# Power.net
KiCad netlist of a schematic drawn in Altium Designer
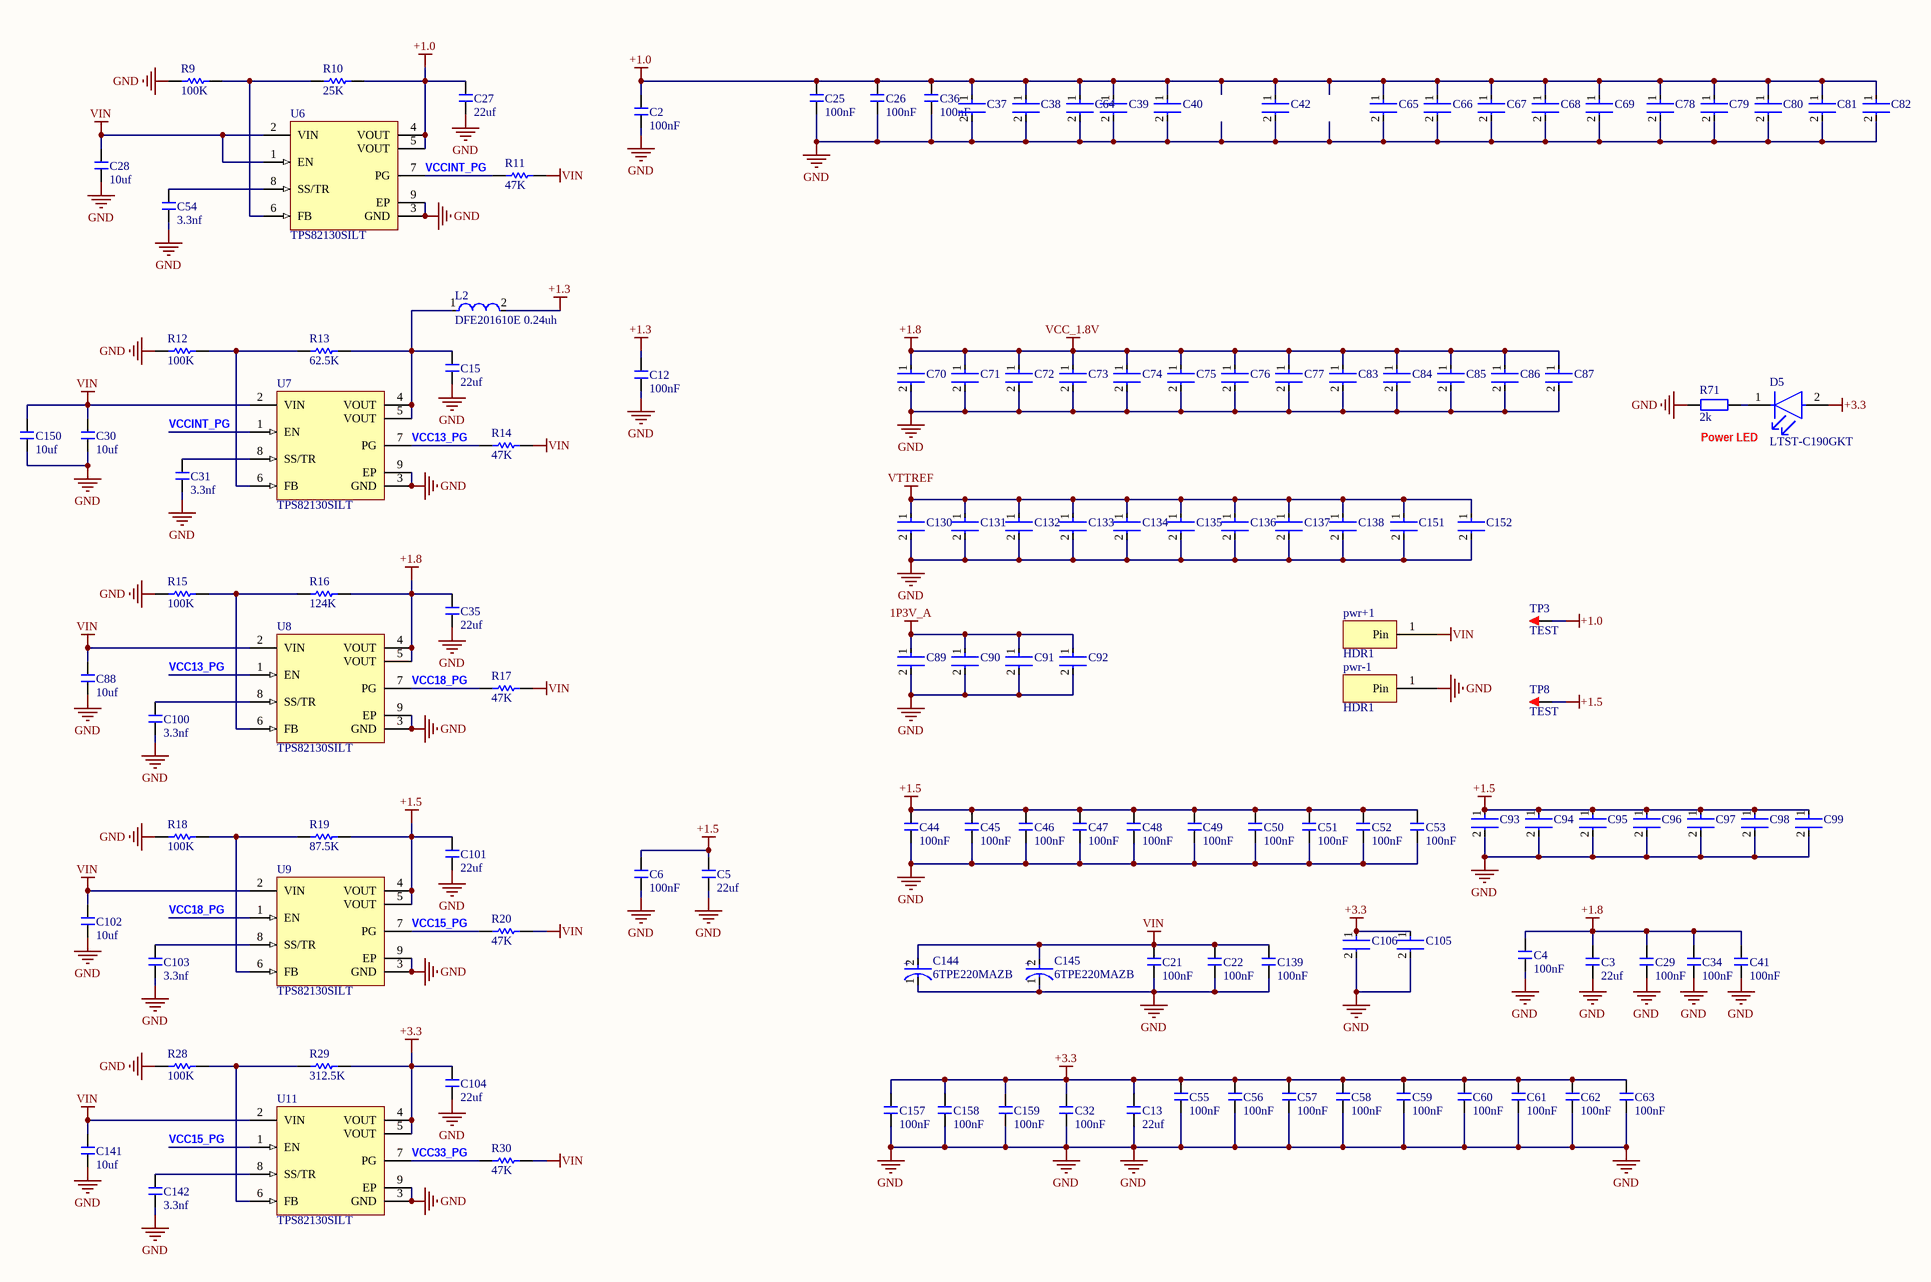
[diagram p0: Power.SchDoc]

(export (version "E")
  (design (tool "Eeschema 10.0.6"))
  (components
    (comp (ref "C2")
      (value "100nF")
      (footprint "SamacSys:CAP_0402")
      (description "无极性贴片电容")
      (libsource (lib "源创客") (part "C"))
    )
    (comp (ref "C3")
      (value "22uf")
      (footprint "SamacSys:CAP_0603")
      (description "无极性贴片电容")
      (libsource (lib "源创客") (part "C"))
    )
    (comp (ref "C4")
      (value "100nF")
      (footprint "SamacSys:CAP_0402")
      (description "无极性贴片电容")
      (libsource (lib "源创客") (part "C"))
    )
    (comp (ref "C5")
      (value "22uf")
      (footprint "SamacSys:CAP_0603")
      (description "无极性贴片电容")
      (libsource (lib "源创客") (part "C"))
    )
    (comp (ref "C6")
      (value "100nF")
      (footprint "SamacSys:CAP_0402")
      (description "无极性贴片电容")
      (libsource (lib "源创客") (part "C"))
    )
    (comp (ref "C12")
      (value "100nF")
      (footprint "SamacSys:CAP_0402")
      (description "无极性贴片电容")
      (libsource (lib "源创客") (part "C"))
    )
    (comp (ref "C13")
      (value "22uf")
      (footprint "SamacSys:CAP_0603")
      (description "无极性贴片电容")
      (libsource (lib "源创客") (part "C"))
    )
    (comp (ref "C15")
      (value "22uf")
      (footprint "SamacSys:CAP_0603")
      (description "无极性贴片电容")
      (libsource (lib "源创客") (part "C"))
    )
    (comp (ref "C21")
      (value "100nF")
      (footprint "SamacSys:CAP_0402")
      (description "无极性贴片电容")
      (libsource (lib "源创客") (part "C"))
    )
    (comp (ref "C22")
      (value "100nF")
      (footprint "SamacSys:CAP_0402")
      (description "无极性贴片电容")
      (libsource (lib "源创客") (part "C"))
    )
    (comp (ref "C25")
      (value "100nF")
      (footprint "SamacSys:CAP_0402")
      (description "无极性贴片电容")
      (libsource (lib "源创客") (part "C"))
    )
    (comp (ref "C26")
      (value "100nF")
      (footprint "SamacSys:CAP_0402")
      (description "无极性贴片电容")
      (libsource (lib "源创客") (part "C"))
    )
    (comp (ref "C27")
      (value "22uf")
      (footprint "SamacSys:CAP_0603")
      (description "无极性贴片电容")
      (libsource (lib "源创客") (part "C"))
    )
    (comp (ref "C28")
      (value "10uf")
      (footprint "SamacSys:CAP_0603")
      (description "无极性贴片电容")
      (libsource (lib "源创客") (part "C"))
    )
    (comp (ref "C29")
      (value "100nF")
      (footprint "SamacSys:CAP_0201")
      (description "无极性贴片电容")
      (libsource (lib "源创客") (part "C"))
    )
    (comp (ref "C30")
      (value "10uf")
      (footprint "SamacSys:CAP_0603")
      (description "无极性贴片电容")
      (libsource (lib "源创客") (part "C"))
    )
    (comp (ref "C31")
      (value "3.3nf")
      (footprint "SamacSys:CAP_0402")
      (description "无极性贴片电容")
      (libsource (lib "源创客") (part "C"))
    )
    (comp (ref "C32")
      (value "100nF")
      (footprint "SamacSys:CAP_0201")
      (description "无极性贴片电容")
      (libsource (lib "源创客") (part "C"))
    )
    (comp (ref "C34")
      (value "100nF")
      (footprint "SamacSys:CAP_0201")
      (description "无极性贴片电容")
      (libsource (lib "源创客") (part "C"))
    )
    (comp (ref "C35")
      (value "22uf")
      (footprint "SamacSys:CAP_0603")
      (description "无极性贴片电容")
      (libsource (lib "源创客") (part "C"))
    )
    (comp (ref "C36")
      (value "100nF")
      (footprint "SamacSys:CAP_0402")
      (description "无极性贴片电容")
      (libsource (lib "源创客") (part "C"))
    )
    (comp (ref "C37")
      (value "GRM033R61A104KE15D")
      (footprint "FP-GRM033-0_03-IPC_C")
      (description "Chip Multilayer Ceramic Capacitors for General Purpose, 0201, 0.10uF, X5R, 15%, 10%, 10V")
      (fields (field (name "TOLERANCE") "10%") (field (name "VOLTAGE") "10V"))
      (libsource (lib "Altium Content Vault") (part "b4654b650e69147ec39a6b967a45e02"))
    )
    (comp (ref "C38")
      (value "GRM033R61A104KE15D")
      (footprint "FP-GRM033-0_03-IPC_C")
      (description "Chip Multilayer Ceramic Capacitors for General Purpose, 0201, 0.10uF, X5R, 15%, 10%, 10V")
      (fields (field (name "TOLERANCE") "10%") (field (name "VOLTAGE") "10V"))
      (libsource (lib "Altium Content Vault") (part "b4654b650e69147ec39a6b967a45e02"))
    )
    (comp (ref "C39")
      (value "GRM033R61A104KE15D")
      (footprint "FP-GRM033-0_03-IPC_C")
      (description "Chip Multilayer Ceramic Capacitors for General Purpose, 0201, 0.10uF, X5R, 15%, 10%, 10V")
      (fields (field (name "TOLERANCE") "10%") (field (name "VOLTAGE") "10V"))
      (libsource (lib "Altium Content Vault") (part "b4654b650e69147ec39a6b967a45e02"))
    )
    (comp (ref "C40")
      (value "GRM033R61A104KE15D")
      (footprint "FP-GRM033-0_03-IPC_C")
      (description "Chip Multilayer Ceramic Capacitors for General Purpose, 0201, 0.10uF, X5R, 15%, 10%, 10V")
      (fields (field (name "TOLERANCE") "10%") (field (name "VOLTAGE") "10V"))
      (libsource (lib "Altium Content Vault") (part "b4654b650e69147ec39a6b967a45e02"))
    )
    (comp (ref "C41")
      (value "100nF")
      (footprint "SamacSys:CAP_0201")
      (description "无极性贴片电容")
      (libsource (lib "源创客") (part "C"))
    )
    (comp (ref "C42")
      (value "GRM033R61A104KE15D")
      (footprint "FP-GRM033-0_03-IPC_C")
      (description "Chip Multilayer Ceramic Capacitors for General Purpose, 0201, 0.10uF, X5R, 15%, 10%, 10V")
      (fields (field (name "TOLERANCE") "10%") (field (name "VOLTAGE") "10V"))
      (libsource (lib "Altium Content Vault") (part "b4654b650e69147ec39a6b967a45e02"))
    )
    (comp (ref "C44")
      (value "100nF")
      (footprint "SamacSys:CAP_0402")
      (description "无极性贴片电容")
      (libsource (lib "源创客") (part "C"))
    )
    (comp (ref "C45")
      (value "100nF")
      (footprint "SamacSys:CAP_0402")
      (description "无极性贴片电容")
      (libsource (lib "源创客") (part "C"))
    )
    (comp (ref "C46")
      (value "100nF")
      (footprint "SamacSys:CAP_0402")
      (description "无极性贴片电容")
      (libsource (lib "源创客") (part "C"))
    )
    (comp (ref "C47")
      (value "100nF")
      (footprint "SamacSys:CAP_0402")
      (description "无极性贴片电容")
      (libsource (lib "源创客") (part "C"))
    )
    (comp (ref "C48")
      (value "100nF")
      (footprint "SamacSys:CAP_0402")
      (description "无极性贴片电容")
      (libsource (lib "源创客") (part "C"))
    )
    (comp (ref "C49")
      (value "100nF")
      (footprint "SamacSys:CAP_0402")
      (description "无极性贴片电容")
      (libsource (lib "源创客") (part "C"))
    )
    (comp (ref "C50")
      (value "100nF")
      (footprint "SamacSys:CAP_0402")
      (description "无极性贴片电容")
      (libsource (lib "源创客") (part "C"))
    )
    (comp (ref "C51")
      (value "100nF")
      (footprint "SamacSys:CAP_0402")
      (description "无极性贴片电容")
      (libsource (lib "源创客") (part "C"))
    )
    (comp (ref "C52")
      (value "100nF")
      (footprint "SamacSys:CAP_0402")
      (description "无极性贴片电容")
      (libsource (lib "源创客") (part "C"))
    )
    (comp (ref "C53")
      (value "100nF")
      (footprint "SamacSys:CAP_0402")
      (description "无极性贴片电容")
      (libsource (lib "源创客") (part "C"))
    )
    (comp (ref "C54")
      (value "3.3nf")
      (footprint "SamacSys:CAP_0402")
      (description "无极性贴片电容")
      (libsource (lib "源创客") (part "C"))
    )
    (comp (ref "C55")
      (value "100nF")
      (footprint "SamacSys:CAP_0402")
      (description "无极性贴片电容")
      (libsource (lib "源创客") (part "C"))
    )
    (comp (ref "C56")
      (value "100nF")
      (footprint "SamacSys:CAP_0402")
      (description "无极性贴片电容")
      (libsource (lib "源创客") (part "C"))
    )
    (comp (ref "C57")
      (value "100nF")
      (footprint "SamacSys:CAP_0402")
      (description "无极性贴片电容")
      (libsource (lib "源创客") (part "C"))
    )
    (comp (ref "C58")
      (value "100nF")
      (footprint "SamacSys:CAP_0402")
      (description "无极性贴片电容")
      (libsource (lib "源创客") (part "C"))
    )
    (comp (ref "C59")
      (value "100nF")
      (footprint "SamacSys:CAP_0201")
      (description "无极性贴片电容")
      (libsource (lib "源创客") (part "C"))
    )
    (comp (ref "C60")
      (value "100nF")
      (footprint "SamacSys:CAP_0201")
      (description "无极性贴片电容")
      (libsource (lib "源创客") (part "C"))
    )
    (comp (ref "C61")
      (value "100nF")
      (footprint "SamacSys:CAP_0201")
      (description "无极性贴片电容")
      (libsource (lib "源创客") (part "C"))
    )
    (comp (ref "C62")
      (value "100nF")
      (footprint "SamacSys:CAP_0402")
      (description "无极性贴片电容")
      (libsource (lib "源创客") (part "C"))
    )
    (comp (ref "C63")
      (value "100nF")
      (footprint "SamacSys:CAP_0402")
      (description "无极性贴片电容")
      (libsource (lib "源创客") (part "C"))
    )
    (comp (ref "C64")
      (value "GRM033R61A104KE15D")
      (footprint "FP-GRM033-0_03-IPC_C")
      (description "Chip Multilayer Ceramic Capacitors for General Purpose, 0201, 0.10uF, X5R, 15%, 10%, 10V")
      (fields (field (name "TOLERANCE") "10%") (field (name "VOLTAGE") "10V"))
      (libsource (lib "Altium Content Vault") (part "b4654b650e69147ec39a6b967a45e02"))
    )
    (comp (ref "C65")
      (value "GRM033R61A104KE15D")
      (footprint "FP-GRM033-0_03-IPC_C")
      (description "Chip Multilayer Ceramic Capacitors for General Purpose, 0201, 0.10uF, X5R, 15%, 10%, 10V")
      (fields (field (name "TOLERANCE") "10%") (field (name "VOLTAGE") "10V"))
      (libsource (lib "Altium Content Vault") (part "b4654b650e69147ec39a6b967a45e02"))
    )
    (comp (ref "C66")
      (value "GRM033R61A104KE15D")
      (footprint "FP-GRM033-0_03-IPC_C")
      (description "Chip Multilayer Ceramic Capacitors for General Purpose, 0201, 0.10uF, X5R, 15%, 10%, 10V")
      (fields (field (name "TOLERANCE") "10%") (field (name "VOLTAGE") "10V"))
      (libsource (lib "Altium Content Vault") (part "b4654b650e69147ec39a6b967a45e02"))
    )
    (comp (ref "C67")
      (value "GRM033R61A104KE15D")
      (footprint "FP-GRM033-0_03-IPC_C")
      (description "Chip Multilayer Ceramic Capacitors for General Purpose, 0201, 0.10uF, X5R, 15%, 10%, 10V")
      (fields (field (name "TOLERANCE") "10%") (field (name "VOLTAGE") "10V"))
      (libsource (lib "Altium Content Vault") (part "b4654b650e69147ec39a6b967a45e02"))
    )
    (comp (ref "C68")
      (value "GRM033R61A104KE15D")
      (footprint "FP-GRM033-0_03-IPC_C")
      (description "Chip Multilayer Ceramic Capacitors for General Purpose, 0201, 0.10uF, X5R, 15%, 10%, 10V")
      (fields (field (name "TOLERANCE") "10%") (field (name "VOLTAGE") "10V"))
      (libsource (lib "Altium Content Vault") (part "b4654b650e69147ec39a6b967a45e02"))
    )
    (comp (ref "C69")
      (value "GRM033R61A104KE15D")
      (footprint "FP-GRM033-0_03-IPC_C")
      (description "Chip Multilayer Ceramic Capacitors for General Purpose, 0201, 0.10uF, X5R, 15%, 10%, 10V")
      (fields (field (name "TOLERANCE") "10%") (field (name "VOLTAGE") "10V"))
      (libsource (lib "Altium Content Vault") (part "b4654b650e69147ec39a6b967a45e02"))
    )
    (comp (ref "C70")
      (value "GRM033R61A104KE15D")
      (footprint "FP-GRM033-0_03-IPC_C")
      (description "Chip Multilayer Ceramic Capacitors for General Purpose, 0201, 0.10uF, X5R, 15%, 10%, 10V")
      (fields (field (name "TOLERANCE") "10%") (field (name "VOLTAGE") "10V"))
      (libsource (lib "Altium Content Vault") (part "b4654b650e69147ec39a6b967a45e02"))
    )
    (comp (ref "C71")
      (value "GRM033R61A104KE15D")
      (footprint "FP-GRM033-0_03-IPC_C")
      (description "Chip Multilayer Ceramic Capacitors for General Purpose, 0201, 0.10uF, X5R, 15%, 10%, 10V")
      (fields (field (name "TOLERANCE") "10%") (field (name "VOLTAGE") "10V"))
      (libsource (lib "Altium Content Vault") (part "b4654b650e69147ec39a6b967a45e02"))
    )
    (comp (ref "C72")
      (value "GRM033R61A104KE15D")
      (footprint "FP-GRM033-0_03-IPC_C")
      (description "Chip Multilayer Ceramic Capacitors for General Purpose, 0201, 0.10uF, X5R, 15%, 10%, 10V")
      (fields (field (name "TOLERANCE") "10%") (field (name "VOLTAGE") "10V"))
      (libsource (lib "Altium Content Vault") (part "b4654b650e69147ec39a6b967a45e02"))
    )
    (comp (ref "C73")
      (value "GRM033R61A104KE15D")
      (footprint "FP-GRM033-0_03-IPC_C")
      (description "Chip Multilayer Ceramic Capacitors for General Purpose, 0201, 0.10uF, X5R, 15%, 10%, 10V")
      (fields (field (name "TOLERANCE") "10%") (field (name "VOLTAGE") "10V"))
      (libsource (lib "Altium Content Vault") (part "b4654b650e69147ec39a6b967a45e02"))
    )
    (comp (ref "C74")
      (value "GRM033R61A104KE15D")
      (footprint "FP-GRM033-0_03-IPC_C")
      (description "Chip Multilayer Ceramic Capacitors for General Purpose, 0201, 0.10uF, X5R, 15%, 10%, 10V")
      (fields (field (name "TOLERANCE") "10%") (field (name "VOLTAGE") "10V"))
      (libsource (lib "Altium Content Vault") (part "b4654b650e69147ec39a6b967a45e02"))
    )
    (comp (ref "C75")
      (value "GRM033R61A104KE15D")
      (footprint "FP-GRM033-0_03-IPC_C")
      (description "Chip Multilayer Ceramic Capacitors for General Purpose, 0201, 0.10uF, X5R, 15%, 10%, 10V")
      (fields (field (name "TOLERANCE") "10%") (field (name "VOLTAGE") "10V"))
      (libsource (lib "Altium Content Vault") (part "b4654b650e69147ec39a6b967a45e02"))
    )
    (comp (ref "C76")
      (value "GRM033R61A104KE15D")
      (footprint "FP-GRM033-0_03-IPC_C")
      (description "Chip Multilayer Ceramic Capacitors for General Purpose, 0201, 0.10uF, X5R, 15%, 10%, 10V")
      (fields (field (name "TOLERANCE") "10%") (field (name "VOLTAGE") "10V"))
      (libsource (lib "Altium Content Vault") (part "b4654b650e69147ec39a6b967a45e02"))
    )
    (comp (ref "C77")
      (value "GRM033R61A104KE15D")
      (footprint "FP-GRM033-0_03-IPC_C")
      (description "Chip Multilayer Ceramic Capacitors for General Purpose, 0201, 0.10uF, X5R, 15%, 10%, 10V")
      (fields (field (name "TOLERANCE") "10%") (field (name "VOLTAGE") "10V"))
      (libsource (lib "Altium Content Vault") (part "b4654b650e69147ec39a6b967a45e02"))
    )
    (comp (ref "C78")
      (value "GRM033R61A104KE15D")
      (footprint "FP-GRM033-0_03-IPC_C")
      (description "Chip Multilayer Ceramic Capacitors for General Purpose, 0201, 0.10uF, X5R, 15%, 10%, 10V")
      (fields (field (name "TOLERANCE") "10%") (field (name "VOLTAGE") "10V"))
      (libsource (lib "Altium Content Vault") (part "b4654b650e69147ec39a6b967a45e02"))
    )
    (comp (ref "C79")
      (value "GRM033R61A104KE15D")
      (footprint "FP-GRM033-0_03-IPC_C")
      (description "Chip Multilayer Ceramic Capacitors for General Purpose, 0201, 0.10uF, X5R, 15%, 10%, 10V")
      (fields (field (name "TOLERANCE") "10%") (field (name "VOLTAGE") "10V"))
      (libsource (lib "Altium Content Vault") (part "b4654b650e69147ec39a6b967a45e02"))
    )
    (comp (ref "C80")
      (value "GRM033R61A104KE15D")
      (footprint "FP-GRM033-0_03-IPC_C")
      (description "Chip Multilayer Ceramic Capacitors for General Purpose, 0201, 0.10uF, X5R, 15%, 10%, 10V")
      (fields (field (name "TOLERANCE") "10%") (field (name "VOLTAGE") "10V"))
      (libsource (lib "Altium Content Vault") (part "b4654b650e69147ec39a6b967a45e02"))
    )
    (comp (ref "C81")
      (value "GRM033R61A104KE15D")
      (footprint "FP-GRM033-0_03-IPC_C")
      (description "Chip Multilayer Ceramic Capacitors for General Purpose, 0201, 0.10uF, X5R, 15%, 10%, 10V")
      (fields (field (name "TOLERANCE") "10%") (field (name "VOLTAGE") "10V"))
      (libsource (lib "Altium Content Vault") (part "b4654b650e69147ec39a6b967a45e02"))
    )
    (comp (ref "C82")
      (value "GRM033R61A104KE15D")
      (footprint "FP-GRM033-0_03-IPC_C")
      (description "Chip Multilayer Ceramic Capacitors for General Purpose, 0201, 0.10uF, X5R, 15%, 10%, 10V")
      (fields (field (name "TOLERANCE") "10%") (field (name "VOLTAGE") "10V"))
      (libsource (lib "Altium Content Vault") (part "b4654b650e69147ec39a6b967a45e02"))
    )
    (comp (ref "C83")
      (value "GRM033R61A104KE15D")
      (footprint "FP-GRM033-0_03-IPC_C")
      (description "Chip Multilayer Ceramic Capacitors for General Purpose, 0201, 0.10uF, X5R, 15%, 10%, 10V")
      (fields (field (name "TOLERANCE") "10%") (field (name "VOLTAGE") "10V"))
      (libsource (lib "Altium Content Vault") (part "b4654b650e69147ec39a6b967a45e02"))
    )
    (comp (ref "C84")
      (value "GRM033R61A104KE15D")
      (footprint "FP-GRM033-0_03-IPC_C")
      (description "Chip Multilayer Ceramic Capacitors for General Purpose, 0201, 0.10uF, X5R, 15%, 10%, 10V")
      (fields (field (name "TOLERANCE") "10%") (field (name "VOLTAGE") "10V"))
      (libsource (lib "Altium Content Vault") (part "b4654b650e69147ec39a6b967a45e02"))
    )
    (comp (ref "C85")
      (value "GRM033R61A104KE15D")
      (footprint "FP-GRM033-0_03-IPC_C")
      (description "Chip Multilayer Ceramic Capacitors for General Purpose, 0201, 0.10uF, X5R, 15%, 10%, 10V")
      (fields (field (name "TOLERANCE") "10%") (field (name "VOLTAGE") "10V"))
      (libsource (lib "Altium Content Vault") (part "b4654b650e69147ec39a6b967a45e02"))
    )
    (comp (ref "C86")
      (value "GRM033R61A104KE15D")
      (footprint "FP-GRM033-0_03-IPC_C")
      (description "Chip Multilayer Ceramic Capacitors for General Purpose, 0201, 0.10uF, X5R, 15%, 10%, 10V")
      (fields (field (name "TOLERANCE") "10%") (field (name "VOLTAGE") "10V"))
      (libsource (lib "Altium Content Vault") (part "b4654b650e69147ec39a6b967a45e02"))
    )
    (comp (ref "C87")
      (value "GRM033R61A104KE15D")
      (footprint "FP-GRM033-0_03-IPC_C")
      (description "Chip Multilayer Ceramic Capacitors for General Purpose, 0201, 0.10uF, X5R, 15%, 10%, 10V")
      (fields (field (name "TOLERANCE") "10%") (field (name "VOLTAGE") "10V"))
      (libsource (lib "Altium Content Vault") (part "b4654b650e69147ec39a6b967a45e02"))
    )
    (comp (ref "C88")
      (value "10uf")
      (footprint "SamacSys:CAP_0603")
      (description "无极性贴片电容")
      (libsource (lib "源创客") (part "C"))
    )
    (comp (ref "C89")
      (value "GRM033R61A104KE15D")
      (footprint "FP-GRM033-0_03-IPC_C")
      (description "Chip Multilayer Ceramic Capacitors for General Purpose, 0201, 0.10uF, X5R, 15%, 10%, 10V")
      (fields (field (name "TOLERANCE") "10%") (field (name "VOLTAGE") "10V"))
      (libsource (lib "Altium Content Vault") (part "b4654b650e69147ec39a6b967a45e02"))
    )
    (comp (ref "C90")
      (value "GRM033R61A104KE15D")
      (footprint "FP-GRM033-0_03-IPC_C")
      (description "Chip Multilayer Ceramic Capacitors for General Purpose, 0201, 0.10uF, X5R, 15%, 10%, 10V")
      (fields (field (name "TOLERANCE") "10%") (field (name "VOLTAGE") "10V"))
      (libsource (lib "Altium Content Vault") (part "b4654b650e69147ec39a6b967a45e02"))
    )
    (comp (ref "C91")
      (value "GRM033R61A104KE15D")
      (footprint "FP-GRM033-0_03-IPC_C")
      (description "Chip Multilayer Ceramic Capacitors for General Purpose, 0201, 0.10uF, X5R, 15%, 10%, 10V")
      (fields (field (name "TOLERANCE") "10%") (field (name "VOLTAGE") "10V"))
      (libsource (lib "Altium Content Vault") (part "b4654b650e69147ec39a6b967a45e02"))
    )
    (comp (ref "C92")
      (value "GRM033R61A104KE15D")
      (footprint "FP-GRM033-0_03-IPC_C")
      (description "Chip Multilayer Ceramic Capacitors for General Purpose, 0201, 0.10uF, X5R, 15%, 10%, 10V")
      (fields (field (name "TOLERANCE") "10%") (field (name "VOLTAGE") "10V"))
      (libsource (lib "Altium Content Vault") (part "b4654b650e69147ec39a6b967a45e02"))
    )
    (comp (ref "C93")
      (value "GRM033R61A104KE15D")
      (footprint "FP-GRM033-0_03-IPC_C")
      (description "Chip Multilayer Ceramic Capacitors for General Purpose, 0201, 0.10uF, X5R, 15%, 10%, 10V")
      (fields (field (name "TOLERANCE") "10%") (field (name "VOLTAGE") "10V"))
      (libsource (lib "Altium Content Vault") (part "b4654b650e69147ec39a6b967a45e02"))
    )
    (comp (ref "C94")
      (value "GRM033R61A104KE15D")
      (footprint "FP-GRM033-0_03-IPC_C")
      (description "Chip Multilayer Ceramic Capacitors for General Purpose, 0201, 0.10uF, X5R, 15%, 10%, 10V")
      (fields (field (name "TOLERANCE") "10%") (field (name "VOLTAGE") "10V"))
      (libsource (lib "Altium Content Vault") (part "b4654b650e69147ec39a6b967a45e02"))
    )
    (comp (ref "C95")
      (value "GRM033R61A104KE15D")
      (footprint "FP-GRM033-0_03-IPC_C")
      (description "Chip Multilayer Ceramic Capacitors for General Purpose, 0201, 0.10uF, X5R, 15%, 10%, 10V")
      (fields (field (name "TOLERANCE") "10%") (field (name "VOLTAGE") "10V"))
      (libsource (lib "Altium Content Vault") (part "b4654b650e69147ec39a6b967a45e02"))
    )
    (comp (ref "C96")
      (value "GRM033R61A104KE15D")
      (footprint "FP-GRM033-0_03-IPC_C")
      (description "Chip Multilayer Ceramic Capacitors for General Purpose, 0201, 0.10uF, X5R, 15%, 10%, 10V")
      (fields (field (name "TOLERANCE") "10%") (field (name "VOLTAGE") "10V"))
      (libsource (lib "Altium Content Vault") (part "b4654b650e69147ec39a6b967a45e02"))
    )
    (comp (ref "C97")
      (value "GRM033R61A104KE15D")
      (footprint "FP-GRM033-0_03-IPC_C")
      (description "Chip Multilayer Ceramic Capacitors for General Purpose, 0201, 0.10uF, X5R, 15%, 10%, 10V")
      (fields (field (name "TOLERANCE") "10%") (field (name "VOLTAGE") "10V"))
      (libsource (lib "Altium Content Vault") (part "b4654b650e69147ec39a6b967a45e02"))
    )
    (comp (ref "C98")
      (value "GRM033R61A104KE15D")
      (footprint "FP-GRM033-0_03-IPC_C")
      (description "Chip Multilayer Ceramic Capacitors for General Purpose, 0201, 0.10uF, X5R, 15%, 10%, 10V")
      (fields (field (name "TOLERANCE") "10%") (field (name "VOLTAGE") "10V"))
      (libsource (lib "Altium Content Vault") (part "b4654b650e69147ec39a6b967a45e02"))
    )
    (comp (ref "C99")
      (value "GRM033R61A104KE15D")
      (footprint "FP-GRM033-0_03-IPC_C")
      (description "Chip Multilayer Ceramic Capacitors for General Purpose, 0201, 0.10uF, X5R, 15%, 10%, 10V")
      (fields (field (name "TOLERANCE") "10%") (field (name "VOLTAGE") "10V"))
      (libsource (lib "Altium Content Vault") (part "b4654b650e69147ec39a6b967a45e02"))
    )
    (comp (ref "C100")
      (value "3.3nf")
      (footprint "SamacSys:CAP_0402")
      (description "无极性贴片电容")
      (libsource (lib "源创客") (part "C"))
    )
    (comp (ref "C101")
      (value "22uf")
      (footprint "SamacSys:CAP_0603")
      (description "无极性贴片电容")
      (libsource (lib "源创客") (part "C"))
    )
    (comp (ref "C102")
      (value "10uf")
      (footprint "SamacSys:CAP_0603")
      (description "无极性贴片电容")
      (libsource (lib "源创客") (part "C"))
    )
    (comp (ref "C103")
      (value "3.3nf")
      (footprint "SamacSys:CAP_0402")
      (description "无极性贴片电容")
      (libsource (lib "源创客") (part "C"))
    )
    (comp (ref "C104")
      (value "22uf")
      (footprint "SamacSys:CAP_0603")
      (description "无极性贴片电容")
      (libsource (lib "源创客") (part "C"))
    )
    (comp (ref "C105")
      (value "GRM033R61A104KE15D")
      (footprint "FP-GRM033-0_03-IPC_C")
      (description "Chip Multilayer Ceramic Capacitors for General Purpose, 0201, 0.10uF, X5R, 15%, 10%, 10V")
      (fields (field (name "TOLERANCE") "10%") (field (name "VOLTAGE") "10V"))
      (libsource (lib "Altium Content Vault") (part "b4654b650e69147ec39a6b967a45e02"))
    )
    (comp (ref "C106")
      (value "GRM033R61A104KE15D")
      (footprint "FP-GRM033-0_03-IPC_C")
      (description "Chip Multilayer Ceramic Capacitors for General Purpose, 0201, 0.10uF, X5R, 15%, 10%, 10V")
      (fields (field (name "TOLERANCE") "10%") (field (name "VOLTAGE") "10V"))
      (libsource (lib "Altium Content Vault") (part "b4654b650e69147ec39a6b967a45e02"))
    )
    (comp (ref "C130")
      (value "GRM033R61A104KE15D")
      (footprint "FP-GRM033-0_03-IPC_C")
      (description "Chip Multilayer Ceramic Capacitors for General Purpose, 0201, 0.10uF, X5R, 15%, 10%, 10V")
      (fields (field (name "TOLERANCE") "10%") (field (name "VOLTAGE") "10V"))
      (libsource (lib "Altium Content Vault") (part "b4654b650e69147ec39a6b967a45e02"))
    )
    (comp (ref "C131")
      (value "GRM033R61A104KE15D")
      (footprint "FP-GRM033-0_03-IPC_C")
      (description "Chip Multilayer Ceramic Capacitors for General Purpose, 0201, 0.10uF, X5R, 15%, 10%, 10V")
      (fields (field (name "TOLERANCE") "10%") (field (name "VOLTAGE") "10V"))
      (libsource (lib "Altium Content Vault") (part "b4654b650e69147ec39a6b967a45e02"))
    )
    (comp (ref "C132")
      (value "GRM033R61A104KE15D")
      (footprint "FP-GRM033-0_03-IPC_C")
      (description "Chip Multilayer Ceramic Capacitors for General Purpose, 0201, 0.10uF, X5R, 15%, 10%, 10V")
      (fields (field (name "TOLERANCE") "10%") (field (name "VOLTAGE") "10V"))
      (libsource (lib "Altium Content Vault") (part "b4654b650e69147ec39a6b967a45e02"))
    )
    (comp (ref "C133")
      (value "GRM033R61A104KE15D")
      (footprint "FP-GRM033-0_03-IPC_C")
      (description "Chip Multilayer Ceramic Capacitors for General Purpose, 0201, 0.10uF, X5R, 15%, 10%, 10V")
      (fields (field (name "TOLERANCE") "10%") (field (name "VOLTAGE") "10V"))
      (libsource (lib "Altium Content Vault") (part "b4654b650e69147ec39a6b967a45e02"))
    )
    (comp (ref "C134")
      (value "GRM033R61A104KE15D")
      (footprint "FP-GRM033-0_03-IPC_C")
      (description "Chip Multilayer Ceramic Capacitors for General Purpose, 0201, 0.10uF, X5R, 15%, 10%, 10V")
      (fields (field (name "TOLERANCE") "10%") (field (name "VOLTAGE") "10V"))
      (libsource (lib "Altium Content Vault") (part "b4654b650e69147ec39a6b967a45e02"))
    )
    (comp (ref "C135")
      (value "GRM033R61A104KE15D")
      (footprint "FP-GRM033-0_03-IPC_C")
      (description "Chip Multilayer Ceramic Capacitors for General Purpose, 0201, 0.10uF, X5R, 15%, 10%, 10V")
      (fields (field (name "TOLERANCE") "10%") (field (name "VOLTAGE") "10V"))
      (libsource (lib "Altium Content Vault") (part "b4654b650e69147ec39a6b967a45e02"))
    )
    (comp (ref "C136")
      (value "GRM033R61A104KE15D")
      (footprint "FP-GRM033-0_03-IPC_C")
      (description "Chip Multilayer Ceramic Capacitors for General Purpose, 0201, 0.10uF, X5R, 15%, 10%, 10V")
      (fields (field (name "TOLERANCE") "10%") (field (name "VOLTAGE") "10V"))
      (libsource (lib "Altium Content Vault") (part "b4654b650e69147ec39a6b967a45e02"))
    )
    (comp (ref "C137")
      (value "GRM033R61A104KE15D")
      (footprint "FP-GRM033-0_03-IPC_C")
      (description "Chip Multilayer Ceramic Capacitors for General Purpose, 0201, 0.10uF, X5R, 15%, 10%, 10V")
      (fields (field (name "TOLERANCE") "10%") (field (name "VOLTAGE") "10V"))
      (libsource (lib "Altium Content Vault") (part "b4654b650e69147ec39a6b967a45e02"))
    )
    (comp (ref "C138")
      (value "GRM033R61A104KE15D")
      (footprint "FP-GRM033-0_03-IPC_C")
      (description "Chip Multilayer Ceramic Capacitors for General Purpose, 0201, 0.10uF, X5R, 15%, 10%, 10V")
      (fields (field (name "TOLERANCE") "10%") (field (name "VOLTAGE") "10V"))
      (libsource (lib "Altium Content Vault") (part "b4654b650e69147ec39a6b967a45e02"))
    )
    (comp (ref "C139")
      (value "100nF")
      (footprint "SamacSys:CAP_0402")
      (description "无极性贴片电容")
      (libsource (lib "源创客") (part "C"))
    )
    (comp (ref "C141")
      (value "10uf")
      (footprint "SamacSys:CAP_0603")
      (description "无极性贴片电容")
      (libsource (lib "源创客") (part "C"))
    )
    (comp (ref "C142")
      (value "3.3nf")
      (footprint "SamacSys:CAP_0402")
      (description "无极性贴片电容")
      (libsource (lib "源创客") (part "C"))
    )
    (comp (ref "C144")
      (value "6TPE220MAZB")
      (footprint "FP-TPEB2-MFG")
      (description "CAP TANT POLY 220UF 6.3V 1411")
      (fields (field (name "TOLERANCE") "20%") (field (name "VOLTAGE") "6.3V"))
      (libsource (lib "Altium Content Vault") (part "a00bbbee19879c290e62620ae7e47b1"))
    )
    (comp (ref "C145")
      (value "6TPE220MAZB")
      (footprint "FP-TPEB2-MFG")
      (description "CAP TANT POLY 220UF 6.3V 1411")
      (fields (field (name "TOLERANCE") "20%") (field (name "VOLTAGE") "6.3V"))
      (libsource (lib "Altium Content Vault") (part "a00bbbee19879c290e62620ae7e47b1"))
    )
    (comp (ref "C150")
      (value "10uf")
      (footprint "SamacSys:CAP_0603")
      (description "无极性贴片电容")
      (libsource (lib "源创客") (part "C"))
    )
    (comp (ref "C151")
      (value "GRM033R61A104KE15D")
      (footprint "FP-GRM033-0_03-IPC_C")
      (description "Chip Multilayer Ceramic Capacitors for General Purpose, 0201, 0.10uF, X5R, 15%, 10%, 10V")
      (fields (field (name "TOLERANCE") "10%") (field (name "VOLTAGE") "10V"))
      (libsource (lib "Altium Content Vault") (part "b4654b650e69147ec39a6b967a45e02"))
    )
    (comp (ref "C152")
      (value "GRM033R61A104KE15D")
      (footprint "FP-GRM033-0_03-IPC_C")
      (description "Chip Multilayer Ceramic Capacitors for General Purpose, 0201, 0.10uF, X5R, 15%, 10%, 10V")
      (fields (field (name "TOLERANCE") "10%") (field (name "VOLTAGE") "10V"))
      (libsource (lib "Altium Content Vault") (part "b4654b650e69147ec39a6b967a45e02"))
    )
    (comp (ref "C157")
      (value "100nF")
      (footprint "SamacSys:CAP_0201")
      (description "无极性贴片电容")
      (libsource (lib "源创客") (part "C"))
    )
    (comp (ref "C158")
      (value "100nF")
      (footprint "SamacSys:CAP_0201")
      (description "无极性贴片电容")
      (libsource (lib "源创客") (part "C"))
    )
    (comp (ref "C159")
      (value "100nF")
      (footprint "SamacSys:CAP_0201")
      (description "无极性贴片电容")
      (libsource (lib "源创客") (part "C"))
    )
    (comp (ref "D5")
      (value "LTST-C190GKT")
      (footprint "FP-LTST-C190GKT-MFG")
      (description "LED GREEN CLEAR CHIP SMD")
      (fields (field (name "VOLTAGE") "2V"))
      (libsource (lib "Altium Content Vault") (part "8706943c75ba83719d021d2fdc84c58"))
    )
    (comp (ref "L2")
      (value "DFE201610E 0.24uh")
      (footprint "FP-DFE201610C-MFG")
      (description "0.24uh")
      (libsource (lib "Altium Content Vault") (part "725321dda6339637d4d059423bc1c3c"))
    )
    (comp (ref "pwr+1") (value "HDR1") (footprint "SamacSys:HDR1") (libsource (lib "SamacSys") (part "HDR1")))
    (comp (ref "pwr-1") (value "HDR1") (footprint "SamacSys:HDR1") (libsource (lib "SamacSys") (part "HDR1")))
    (comp (ref "R9") (value "100K") (footprint "SamacSys:RES_0402") (libsource (lib "电阻") (part "RES")))
    (comp (ref "R10") (value "25K") (footprint "SamacSys:RES_0402") (libsource (lib "电阻") (part "RES")))
    (comp (ref "R11") (value "47K") (footprint "SamacSys:RES_0402") (libsource (lib "电阻") (part "RES")))
    (comp (ref "R12") (value "100K") (footprint "SamacSys:RES_0402") (libsource (lib "电阻") (part "RES")))
    (comp (ref "R13") (value "62.5K") (footprint "SamacSys:RES_0402") (libsource (lib "电阻") (part "RES")))
    (comp (ref "R14") (value "47K") (footprint "SamacSys:RES_0402") (libsource (lib "电阻") (part "RES")))
    (comp (ref "R15") (value "100K") (footprint "SamacSys:RES_0402") (libsource (lib "电阻") (part "RES")))
    (comp (ref "R16") (value "124K") (footprint "SamacSys:RES_0402") (libsource (lib "电阻") (part "RES")))
    (comp (ref "R17") (value "47K") (footprint "SamacSys:RES_0402") (libsource (lib "电阻") (part "RES")))
    (comp (ref "R18") (value "100K") (footprint "SamacSys:RES_0402") (libsource (lib "电阻") (part "RES")))
    (comp (ref "R19") (value "87.5K") (footprint "SamacSys:RES_0402") (libsource (lib "电阻") (part "RES")))
    (comp (ref "R20") (value "47K") (footprint "SamacSys:RES_0402") (libsource (lib "电阻") (part "RES")))
    (comp (ref "R28") (value "100K") (footprint "SamacSys:RES_0402") (libsource (lib "电阻") (part "RES")))
    (comp (ref "R29") (value "312.5K") (footprint "SamacSys:RES_0402") (libsource (lib "电阻") (part "RES")))
    (comp (ref "R30") (value "47K") (footprint "SamacSys:RES_0402") (libsource (lib "电阻") (part "RES")))
    (comp (ref "R71")
      (value "2k")
      (footprint "SamacSys:RES_0402")
      (description "贴片电阻")
      (libsource (lib "源创客") (part "R"))
    )
    (comp (ref "TP3")
      (value "TEST")
      (footprint "TEST 0.8")
      (description "测试点")
      (libsource (lib "源创客") (part "TEST"))
    )
    (comp (ref "TP8")
      (value "TEST")
      (footprint "TEST 0.8")
      (description "测试点")
      (libsource (lib "源创客") (part "TEST"))
    )
    (comp (ref "U6")
      (value "TPS82130SILT")
      (footprint "SIL0008D_V")
      (fields (field (name "MANUFACTURER") "Texas Instruments"))
      (libsource (lib "Altium Content Vault") (part "TI-TPS82130-SIL-8"))
    )
    (comp (ref "U7")
      (value "TPS82130SILT")
      (footprint "SIL0008D_V")
      (fields (field (name "MANUFACTURER") "Texas Instruments"))
      (libsource (lib "Altium Content Vault") (part "TI-TPS82130-SIL-8"))
    )
    (comp (ref "U8")
      (value "TPS82130SILT")
      (footprint "SIL0008D_V")
      (fields (field (name "MANUFACTURER") "Texas Instruments"))
      (libsource (lib "Altium Content Vault") (part "TI-TPS82130-SIL-8"))
    )
    (comp (ref "U9")
      (value "TPS82130SILT")
      (footprint "SIL0008D_V")
      (fields (field (name "MANUFACTURER") "Texas Instruments"))
      (libsource (lib "Altium Content Vault") (part "TI-TPS82130-SIL-8"))
    )
    (comp (ref "U11")
      (value "TPS82130SILT")
      (footprint "SIL0008D_V")
      (fields (field (name "MANUFACTURER") "Texas Instruments"))
      (libsource (lib "Altium Content Vault") (part "TI-TPS82130-SIL-8"))
    )
  )
  (nets
    (net (code "1") (name "+1.0") (class "Default")
      (node (ref "C2") (pin "1") (pinfunction "1_1") (pintype "passive"))
      (node (ref "C25") (pin "1") (pinfunction "1_1") (pintype "passive"))
      (node (ref "C26") (pin "1") (pinfunction "1_1") (pintype "passive"))
      (node (ref "C27") (pin "2") (pinfunction "2_2") (pintype "passive"))
      (node (ref "C36") (pin "1") (pinfunction "1_1") (pintype "passive"))
      (node (ref "C37") (pin "1") (pinfunction "1_1") (pintype "passive"))
      (node (ref "C38") (pin "1") (pinfunction "1_1") (pintype "passive"))
      (node (ref "C39") (pin "1") (pinfunction "1_1") (pintype "passive"))
      (node (ref "C40") (pin "1") (pinfunction "1_1") (pintype "passive"))
      (node (ref "C42") (pin "1") (pinfunction "1_1") (pintype "passive"))
      (node (ref "C64") (pin "1") (pinfunction "1_1") (pintype "passive"))
      (node (ref "C65") (pin "1") (pinfunction "1_1") (pintype "passive"))
      (node (ref "C66") (pin "1") (pinfunction "1_1") (pintype "passive"))
      (node (ref "C67") (pin "1") (pinfunction "1_1") (pintype "passive"))
      (node (ref "C68") (pin "1") (pinfunction "1_1") (pintype "passive"))
      (node (ref "C69") (pin "1") (pinfunction "1_1") (pintype "passive"))
      (node (ref "C78") (pin "1") (pinfunction "1_1") (pintype "passive"))
      (node (ref "C79") (pin "1") (pinfunction "1_1") (pintype "passive"))
      (node (ref "C80") (pin "1") (pinfunction "1_1") (pintype "passive"))
      (node (ref "C81") (pin "1") (pinfunction "1_1") (pintype "passive"))
      (node (ref "C82") (pin "1") (pinfunction "1_1") (pintype "passive"))
      (node (ref "R10") (pin "1") (pinfunction "1_1") (pintype "passive"))
      (node (ref "TP3") (pin "1") (pinfunction "1_1") (pintype "passive"))
      (node (ref "U6") (pin "4") (pinfunction "VOUT_4") (pintype "power_in"))
      (node (ref "U6") (pin "5") (pinfunction "VOUT_5") (pintype "power_in"))
    )
    (net (code "2") (name "+1.3") (class "Default")
      (node (ref "C12") (pin "1") (pinfunction "1_1") (pintype "passive"))
      (node (ref "L2") (pin "2") (pinfunction "2_2") (pintype "passive"))
    )
    (net (code "3") (name "+1.5") (class "Default")
      (node (ref "C101") (pin "2") (pinfunction "2_2") (pintype "passive"))
      (node (ref "C44") (pin "1") (pinfunction "1_1") (pintype "passive"))
      (node (ref "C45") (pin "1") (pinfunction "1_1") (pintype "passive"))
      (node (ref "C46") (pin "1") (pinfunction "1_1") (pintype "passive"))
      (node (ref "C47") (pin "1") (pinfunction "1_1") (pintype "passive"))
      (node (ref "C48") (pin "1") (pinfunction "1_1") (pintype "passive"))
      (node (ref "C49") (pin "1") (pinfunction "1_1") (pintype "passive"))
      (node (ref "C5") (pin "2") (pinfunction "2_2") (pintype "passive"))
      (node (ref "C50") (pin "1") (pinfunction "1_1") (pintype "passive"))
      (node (ref "C51") (pin "1") (pinfunction "1_1") (pintype "passive"))
      (node (ref "C52") (pin "1") (pinfunction "1_1") (pintype "passive"))
      (node (ref "C53") (pin "1") (pinfunction "1_1") (pintype "passive"))
      (node (ref "C6") (pin "1") (pinfunction "1_1") (pintype "passive"))
      (node (ref "C93") (pin "1") (pinfunction "1_1") (pintype "passive"))
      (node (ref "C94") (pin "1") (pinfunction "1_1") (pintype "passive"))
      (node (ref "C95") (pin "1") (pinfunction "1_1") (pintype "passive"))
      (node (ref "C96") (pin "1") (pinfunction "1_1") (pintype "passive"))
      (node (ref "C97") (pin "1") (pinfunction "1_1") (pintype "passive"))
      (node (ref "C98") (pin "1") (pinfunction "1_1") (pintype "passive"))
      (node (ref "C99") (pin "1") (pinfunction "1_1") (pintype "passive"))
      (node (ref "R19") (pin "1") (pinfunction "1_1") (pintype "passive"))
      (node (ref "TP8") (pin "1") (pinfunction "1_1") (pintype "passive"))
      (node (ref "U9") (pin "4") (pinfunction "VOUT_4") (pintype "power_in"))
      (node (ref "U9") (pin "5") (pinfunction "VOUT_5") (pintype "power_in"))
    )
    (net (code "4") (name "+1.8") (class "Default")
      (node (ref "C29") (pin "1") (pinfunction "1_1") (pintype "passive"))
      (node (ref "C3") (pin "2") (pinfunction "2_2") (pintype "passive"))
      (node (ref "C34") (pin "1") (pinfunction "1_1") (pintype "passive"))
      (node (ref "C35") (pin "2") (pinfunction "2_2") (pintype "passive"))
      (node (ref "C4") (pin "1") (pinfunction "1_1") (pintype "passive"))
      (node (ref "C41") (pin "1") (pinfunction "1_1") (pintype "passive"))
      (node (ref "C70") (pin "1") (pinfunction "1_1") (pintype "passive"))
      (node (ref "C71") (pin "1") (pinfunction "1_1") (pintype "passive"))
      (node (ref "C72") (pin "1") (pinfunction "1_1") (pintype "passive"))
      (node (ref "C73") (pin "1") (pinfunction "1_1") (pintype "passive"))
      (node (ref "C74") (pin "1") (pinfunction "1_1") (pintype "passive"))
      (node (ref "C75") (pin "1") (pinfunction "1_1") (pintype "passive"))
      (node (ref "C76") (pin "1") (pinfunction "1_1") (pintype "passive"))
      (node (ref "C77") (pin "1") (pinfunction "1_1") (pintype "passive"))
      (node (ref "C83") (pin "1") (pinfunction "1_1") (pintype "passive"))
      (node (ref "C84") (pin "1") (pinfunction "1_1") (pintype "passive"))
      (node (ref "C85") (pin "1") (pinfunction "1_1") (pintype "passive"))
      (node (ref "C86") (pin "1") (pinfunction "1_1") (pintype "passive"))
      (node (ref "C87") (pin "1") (pinfunction "1_1") (pintype "passive"))
      (node (ref "R16") (pin "1") (pinfunction "1_1") (pintype "passive"))
      (node (ref "U8") (pin "4") (pinfunction "VOUT_4") (pintype "power_in"))
      (node (ref "U8") (pin "5") (pinfunction "VOUT_5") (pintype "power_in"))
    )
    (net (code "5") (name "+3.3") (class "Default")
      (node (ref "C104") (pin "2") (pinfunction "2_2") (pintype "passive"))
      (node (ref "C105") (pin "1") (pinfunction "1_1") (pintype "passive"))
      (node (ref "C106") (pin "1") (pinfunction "1_1") (pintype "passive"))
      (node (ref "C13") (pin "2") (pinfunction "2_2") (pintype "passive"))
      (node (ref "C157") (pin "1") (pinfunction "1_1") (pintype "passive"))
      (node (ref "C158") (pin "1") (pinfunction "1_1") (pintype "passive"))
      (node (ref "C159") (pin "1") (pinfunction "1_1") (pintype "passive"))
      (node (ref "C32") (pin "1") (pinfunction "1_1") (pintype "passive"))
      (node (ref "C55") (pin "1") (pinfunction "1_1") (pintype "passive"))
      (node (ref "C56") (pin "1") (pinfunction "1_1") (pintype "passive"))
      (node (ref "C57") (pin "1") (pinfunction "1_1") (pintype "passive"))
      (node (ref "C58") (pin "1") (pinfunction "1_1") (pintype "passive"))
      (node (ref "C59") (pin "1") (pinfunction "1_1") (pintype "passive"))
      (node (ref "C60") (pin "1") (pinfunction "1_1") (pintype "passive"))
      (node (ref "C61") (pin "1") (pinfunction "1_1") (pintype "passive"))
      (node (ref "C62") (pin "1") (pinfunction "1_1") (pintype "passive"))
      (node (ref "C63") (pin "1") (pinfunction "1_1") (pintype "passive"))
      (node (ref "D5") (pin "2") (pinfunction "A_2") (pintype "passive"))
      (node (ref "R29") (pin "1") (pinfunction "1_1") (pintype "passive"))
      (node (ref "U11") (pin "4") (pinfunction "VOUT_4") (pintype "power_in"))
      (node (ref "U11") (pin "5") (pinfunction "VOUT_5") (pintype "power_in"))
    )
    (net (code "6") (name "/VCC13_PG") (class "Default")
      (node (ref "R14") (pin "2") (pinfunction "2_2") (pintype "passive"))
      (node (ref "U7") (pin "7") (pinfunction "PG_7") (pintype "open_collector"))
      (node (ref "U8") (pin "1") (pinfunction "EN_1") (pintype "input"))
    )
    (net (code "7") (name "/VCC15_PG") (class "Default")
      (node (ref "R20") (pin "2") (pinfunction "2_2") (pintype "passive"))
      (node (ref "U11") (pin "1") (pinfunction "EN_1") (pintype "input"))
      (node (ref "U9") (pin "7") (pinfunction "PG_7") (pintype "open_collector"))
    )
    (net (code "8") (name "/VCC18_PG") (class "Default")
      (node (ref "R17") (pin "2") (pinfunction "2_2") (pintype "passive"))
      (node (ref "U8") (pin "7") (pinfunction "PG_7") (pintype "open_collector"))
      (node (ref "U9") (pin "1") (pinfunction "EN_1") (pintype "input"))
    )
    (net (code "9") (name "/VCC33_PG") (class "Default")
      (node (ref "R30") (pin "2") (pinfunction "2_2") (pintype "passive"))
      (node (ref "U11") (pin "7") (pinfunction "PG_7") (pintype "open_collector"))
    )
    (net (code "10") (name "/VCCINT_PG") (class "Default")
      (node (ref "R11") (pin "2") (pinfunction "2_2") (pintype "passive"))
      (node (ref "U6") (pin "7") (pinfunction "PG_7") (pintype "open_collector"))
      (node (ref "U7") (pin "1") (pinfunction "EN_1") (pintype "input"))
    )
    (net (code "11") (name "1P3V_A") (class "Default")
      (node (ref "C89") (pin "1") (pinfunction "1_1") (pintype "passive"))
      (node (ref "C90") (pin "1") (pinfunction "1_1") (pintype "passive"))
      (node (ref "C91") (pin "1") (pinfunction "1_1") (pintype "passive"))
      (node (ref "C92") (pin "1") (pinfunction "1_1") (pintype "passive"))
    )
    (net (code "12") (name "GND") (class "Default")
      (node (ref "C100") (pin "1") (pinfunction "1_1") (pintype "passive"))
      (node (ref "C101") (pin "1") (pinfunction "1_1") (pintype "passive"))
      (node (ref "C102") (pin "1") (pinfunction "1_1") (pintype "passive"))
      (node (ref "C103") (pin "1") (pinfunction "1_1") (pintype "passive"))
      (node (ref "C104") (pin "1") (pinfunction "1_1") (pintype "passive"))
      (node (ref "C105") (pin "2") (pinfunction "2_2") (pintype "passive"))
      (node (ref "C106") (pin "2") (pinfunction "2_2") (pintype "passive"))
      (node (ref "C12") (pin "2") (pinfunction "2_2") (pintype "passive"))
      (node (ref "C13") (pin "1") (pinfunction "1_1") (pintype "passive"))
      (node (ref "C130") (pin "2") (pinfunction "2_2") (pintype "passive"))
      (node (ref "C131") (pin "2") (pinfunction "2_2") (pintype "passive"))
      (node (ref "C132") (pin "2") (pinfunction "2_2") (pintype "passive"))
      (node (ref "C133") (pin "2") (pinfunction "2_2") (pintype "passive"))
      (node (ref "C134") (pin "2") (pinfunction "2_2") (pintype "passive"))
      (node (ref "C135") (pin "2") (pinfunction "2_2") (pintype "passive"))
      (node (ref "C136") (pin "2") (pinfunction "2_2") (pintype "passive"))
      (node (ref "C137") (pin "2") (pinfunction "2_2") (pintype "passive"))
      (node (ref "C138") (pin "2") (pinfunction "2_2") (pintype "passive"))
      (node (ref "C139") (pin "2") (pinfunction "2_2") (pintype "passive"))
      (node (ref "C141") (pin "1") (pinfunction "1_1") (pintype "passive"))
      (node (ref "C142") (pin "1") (pinfunction "1_1") (pintype "passive"))
      (node (ref "C144") (pin "1") (pinfunction "C_1") (pintype "passive"))
      (node (ref "C145") (pin "1") (pinfunction "C_1") (pintype "passive"))
      (node (ref "C15") (pin "1") (pinfunction "1_1") (pintype "passive"))
      (node (ref "C150") (pin "1") (pinfunction "1_1") (pintype "passive"))
      (node (ref "C151") (pin "2") (pinfunction "2_2") (pintype "passive"))
      (node (ref "C152") (pin "2") (pinfunction "2_2") (pintype "passive"))
      (node (ref "C157") (pin "2") (pinfunction "2_2") (pintype "passive"))
      (node (ref "C158") (pin "2") (pinfunction "2_2") (pintype "passive"))
      (node (ref "C159") (pin "2") (pinfunction "2_2") (pintype "passive"))
      (node (ref "C2") (pin "2") (pinfunction "2_2") (pintype "passive"))
      (node (ref "C21") (pin "2") (pinfunction "2_2") (pintype "passive"))
      (node (ref "C22") (pin "2") (pinfunction "2_2") (pintype "passive"))
      (node (ref "C25") (pin "2") (pinfunction "2_2") (pintype "passive"))
      (node (ref "C26") (pin "2") (pinfunction "2_2") (pintype "passive"))
      (node (ref "C27") (pin "1") (pinfunction "1_1") (pintype "passive"))
      (node (ref "C28") (pin "1") (pinfunction "1_1") (pintype "passive"))
      (node (ref "C29") (pin "2") (pinfunction "2_2") (pintype "passive"))
      (node (ref "C3") (pin "1") (pinfunction "1_1") (pintype "passive"))
      (node (ref "C30") (pin "1") (pinfunction "1_1") (pintype "passive"))
      (node (ref "C31") (pin "1") (pinfunction "1_1") (pintype "passive"))
      (node (ref "C32") (pin "2") (pinfunction "2_2") (pintype "passive"))
      (node (ref "C34") (pin "2") (pinfunction "2_2") (pintype "passive"))
      (node (ref "C35") (pin "1") (pinfunction "1_1") (pintype "passive"))
      (node (ref "C36") (pin "2") (pinfunction "2_2") (pintype "passive"))
      (node (ref "C37") (pin "2") (pinfunction "2_2") (pintype "passive"))
      (node (ref "C38") (pin "2") (pinfunction "2_2") (pintype "passive"))
      (node (ref "C39") (pin "2") (pinfunction "2_2") (pintype "passive"))
      (node (ref "C4") (pin "2") (pinfunction "2_2") (pintype "passive"))
      (node (ref "C40") (pin "2") (pinfunction "2_2") (pintype "passive"))
      (node (ref "C41") (pin "2") (pinfunction "2_2") (pintype "passive"))
      (node (ref "C42") (pin "2") (pinfunction "2_2") (pintype "passive"))
      (node (ref "C44") (pin "2") (pinfunction "2_2") (pintype "passive"))
      (node (ref "C45") (pin "2") (pinfunction "2_2") (pintype "passive"))
      (node (ref "C46") (pin "2") (pinfunction "2_2") (pintype "passive"))
      (node (ref "C47") (pin "2") (pinfunction "2_2") (pintype "passive"))
      (node (ref "C48") (pin "2") (pinfunction "2_2") (pintype "passive"))
      (node (ref "C49") (pin "2") (pinfunction "2_2") (pintype "passive"))
      (node (ref "C5") (pin "1") (pinfunction "1_1") (pintype "passive"))
      (node (ref "C50") (pin "2") (pinfunction "2_2") (pintype "passive"))
      (node (ref "C51") (pin "2") (pinfunction "2_2") (pintype "passive"))
      (node (ref "C52") (pin "2") (pinfunction "2_2") (pintype "passive"))
      (node (ref "C53") (pin "2") (pinfunction "2_2") (pintype "passive"))
      (node (ref "C54") (pin "1") (pinfunction "1_1") (pintype "passive"))
      (node (ref "C55") (pin "2") (pinfunction "2_2") (pintype "passive"))
      (node (ref "C56") (pin "2") (pinfunction "2_2") (pintype "passive"))
      (node (ref "C57") (pin "2") (pinfunction "2_2") (pintype "passive"))
      (node (ref "C58") (pin "2") (pinfunction "2_2") (pintype "passive"))
      (node (ref "C59") (pin "2") (pinfunction "2_2") (pintype "passive"))
      (node (ref "C6") (pin "2") (pinfunction "2_2") (pintype "passive"))
      (node (ref "C60") (pin "2") (pinfunction "2_2") (pintype "passive"))
      (node (ref "C61") (pin "2") (pinfunction "2_2") (pintype "passive"))
      (node (ref "C62") (pin "2") (pinfunction "2_2") (pintype "passive"))
      (node (ref "C63") (pin "2") (pinfunction "2_2") (pintype "passive"))
      (node (ref "C64") (pin "2") (pinfunction "2_2") (pintype "passive"))
      (node (ref "C65") (pin "2") (pinfunction "2_2") (pintype "passive"))
      (node (ref "C66") (pin "2") (pinfunction "2_2") (pintype "passive"))
      (node (ref "C67") (pin "2") (pinfunction "2_2") (pintype "passive"))
      (node (ref "C68") (pin "2") (pinfunction "2_2") (pintype "passive"))
      (node (ref "C69") (pin "2") (pinfunction "2_2") (pintype "passive"))
      (node (ref "C70") (pin "2") (pinfunction "2_2") (pintype "passive"))
      (node (ref "C71") (pin "2") (pinfunction "2_2") (pintype "passive"))
      (node (ref "C72") (pin "2") (pinfunction "2_2") (pintype "passive"))
      (node (ref "C73") (pin "2") (pinfunction "2_2") (pintype "passive"))
      (node (ref "C74") (pin "2") (pinfunction "2_2") (pintype "passive"))
      (node (ref "C75") (pin "2") (pinfunction "2_2") (pintype "passive"))
      (node (ref "C76") (pin "2") (pinfunction "2_2") (pintype "passive"))
      (node (ref "C77") (pin "2") (pinfunction "2_2") (pintype "passive"))
      (node (ref "C78") (pin "2") (pinfunction "2_2") (pintype "passive"))
      (node (ref "C79") (pin "2") (pinfunction "2_2") (pintype "passive"))
      (node (ref "C80") (pin "2") (pinfunction "2_2") (pintype "passive"))
      (node (ref "C81") (pin "2") (pinfunction "2_2") (pintype "passive"))
      (node (ref "C82") (pin "2") (pinfunction "2_2") (pintype "passive"))
      (node (ref "C83") (pin "2") (pinfunction "2_2") (pintype "passive"))
      (node (ref "C84") (pin "2") (pinfunction "2_2") (pintype "passive"))
      (node (ref "C85") (pin "2") (pinfunction "2_2") (pintype "passive"))
      (node (ref "C86") (pin "2") (pinfunction "2_2") (pintype "passive"))
      (node (ref "C87") (pin "2") (pinfunction "2_2") (pintype "passive"))
      (node (ref "C88") (pin "1") (pinfunction "1_1") (pintype "passive"))
      (node (ref "C89") (pin "2") (pinfunction "2_2") (pintype "passive"))
      (node (ref "C90") (pin "2") (pinfunction "2_2") (pintype "passive"))
      (node (ref "C91") (pin "2") (pinfunction "2_2") (pintype "passive"))
      (node (ref "C92") (pin "2") (pinfunction "2_2") (pintype "passive"))
      (node (ref "C93") (pin "2") (pinfunction "2_2") (pintype "passive"))
      (node (ref "C94") (pin "2") (pinfunction "2_2") (pintype "passive"))
      (node (ref "C95") (pin "2") (pinfunction "2_2") (pintype "passive"))
      (node (ref "C96") (pin "2") (pinfunction "2_2") (pintype "passive"))
      (node (ref "C97") (pin "2") (pinfunction "2_2") (pintype "passive"))
      (node (ref "C98") (pin "2") (pinfunction "2_2") (pintype "passive"))
      (node (ref "C99") (pin "2") (pinfunction "2_2") (pintype "passive"))
      (node (ref "R12") (pin "2") (pinfunction "2_2") (pintype "passive"))
      (node (ref "R15") (pin "2") (pinfunction "2_2") (pintype "passive"))
      (node (ref "R18") (pin "2") (pinfunction "2_2") (pintype "passive"))
      (node (ref "R28") (pin "2") (pinfunction "2_2") (pintype "passive"))
      (node (ref "R71") (pin "1") (pinfunction "1_1") (pintype "passive"))
      (node (ref "R9") (pin "2") (pinfunction "2_2") (pintype "passive"))
      (node (ref "U11") (pin "3") (pinfunction "GND_3") (pintype "power_in"))
      (node (ref "U11") (pin "9") (pinfunction "EP_9") (pintype "power_in"))
      (node (ref "U6") (pin "3") (pinfunction "GND_3") (pintype "power_in"))
      (node (ref "U6") (pin "9") (pinfunction "EP_9") (pintype "power_in"))
      (node (ref "U7") (pin "3") (pinfunction "GND_3") (pintype "power_in"))
      (node (ref "U7") (pin "9") (pinfunction "EP_9") (pintype "power_in"))
      (node (ref "U8") (pin "3") (pinfunction "GND_3") (pintype "power_in"))
      (node (ref "U8") (pin "9") (pinfunction "EP_9") (pintype "power_in"))
      (node (ref "U9") (pin "3") (pinfunction "GND_3") (pintype "power_in"))
      (node (ref "U9") (pin "9") (pinfunction "EP_9") (pintype "power_in"))
      (node (ref "pwr-1") (pin "1") (pinfunction "Pin_1") (pintype "passive"))
    )
    (net (code "13") (name "Net-(C15-Pad2)") (class "Default")
      (node (ref "C15") (pin "2") (pinfunction "2_2") (pintype "passive"))
      (node (ref "L2") (pin "1") (pinfunction "1_1") (pintype "passive"))
      (node (ref "R13") (pin "1") (pinfunction "1_1") (pintype "passive"))
      (node (ref "U7") (pin "4") (pinfunction "VOUT_4") (pintype "power_in"))
      (node (ref "U7") (pin "5") (pinfunction "VOUT_5") (pintype "power_in"))
    )
    (net (code "14") (name "Net-(D5-C)") (class "Default")
      (node (ref "D5") (pin "1") (pinfunction "C_1") (pintype "passive"))
      (node (ref "R71") (pin "2") (pinfunction "2_2") (pintype "passive"))
    )
    (net (code "15") (name "Net-(U6-FB)") (class "Default")
      (node (ref "R10") (pin "2") (pinfunction "2_2") (pintype "passive"))
      (node (ref "R9") (pin "1") (pinfunction "1_1") (pintype "passive"))
      (node (ref "U6") (pin "6") (pinfunction "FB_6") (pintype "input"))
    )
    (net (code "16") (name "Net-(U6-SS{slash}TR)") (class "Default")
      (node (ref "C54") (pin "2") (pinfunction "2_2") (pintype "passive"))
      (node (ref "U6") (pin "8") (pinfunction "SS/TR_8") (pintype "input"))
    )
    (net (code "17") (name "Net-(U7-FB)") (class "Default")
      (node (ref "R12") (pin "1") (pinfunction "1_1") (pintype "passive"))
      (node (ref "R13") (pin "2") (pinfunction "2_2") (pintype "passive"))
      (node (ref "U7") (pin "6") (pinfunction "FB_6") (pintype "input"))
    )
    (net (code "18") (name "Net-(U7-SS{slash}TR)") (class "Default")
      (node (ref "C31") (pin "2") (pinfunction "2_2") (pintype "passive"))
      (node (ref "U7") (pin "8") (pinfunction "SS/TR_8") (pintype "input"))
    )
    (net (code "19") (name "Net-(U8-FB)") (class "Default")
      (node (ref "R15") (pin "1") (pinfunction "1_1") (pintype "passive"))
      (node (ref "R16") (pin "2") (pinfunction "2_2") (pintype "passive"))
      (node (ref "U8") (pin "6") (pinfunction "FB_6") (pintype "input"))
    )
    (net (code "20") (name "Net-(U8-SS{slash}TR)") (class "Default")
      (node (ref "C100") (pin "2") (pinfunction "2_2") (pintype "passive"))
      (node (ref "U8") (pin "8") (pinfunction "SS/TR_8") (pintype "input"))
    )
    (net (code "21") (name "Net-(U9-FB)") (class "Default")
      (node (ref "R18") (pin "1") (pinfunction "1_1") (pintype "passive"))
      (node (ref "R19") (pin "2") (pinfunction "2_2") (pintype "passive"))
      (node (ref "U9") (pin "6") (pinfunction "FB_6") (pintype "input"))
    )
    (net (code "22") (name "Net-(U9-SS{slash}TR)") (class "Default")
      (node (ref "C103") (pin "2") (pinfunction "2_2") (pintype "passive"))
      (node (ref "U9") (pin "8") (pinfunction "SS/TR_8") (pintype "input"))
    )
    (net (code "23") (name "Net-(U11-FB)") (class "Default")
      (node (ref "R28") (pin "1") (pinfunction "1_1") (pintype "passive"))
      (node (ref "R29") (pin "2") (pinfunction "2_2") (pintype "passive"))
      (node (ref "U11") (pin "6") (pinfunction "FB_6") (pintype "input"))
    )
    (net (code "24") (name "Net-(U11-SS{slash}TR)") (class "Default")
      (node (ref "C142") (pin "2") (pinfunction "2_2") (pintype "passive"))
      (node (ref "U11") (pin "8") (pinfunction "SS/TR_8") (pintype "input"))
    )
    (net (code "25") (name "VIN") (class "Default")
      (node (ref "C102") (pin "2") (pinfunction "2_2") (pintype "passive"))
      (node (ref "C139") (pin "1") (pinfunction "1_1") (pintype "passive"))
      (node (ref "C141") (pin "2") (pinfunction "2_2") (pintype "passive"))
      (node (ref "C144") (pin "2") (pinfunction "A_2") (pintype "passive"))
      (node (ref "C145") (pin "2") (pinfunction "A_2") (pintype "passive"))
      (node (ref "C150") (pin "2") (pinfunction "2_2") (pintype "passive"))
      (node (ref "C21") (pin "1") (pinfunction "1_1") (pintype "passive"))
      (node (ref "C22") (pin "1") (pinfunction "1_1") (pintype "passive"))
      (node (ref "C28") (pin "2") (pinfunction "2_2") (pintype "passive"))
      (node (ref "C30") (pin "2") (pinfunction "2_2") (pintype "passive"))
      (node (ref "C88") (pin "2") (pinfunction "2_2") (pintype "passive"))
      (node (ref "R11") (pin "1") (pinfunction "1_1") (pintype "passive"))
      (node (ref "R14") (pin "1") (pinfunction "1_1") (pintype "passive"))
      (node (ref "R17") (pin "1") (pinfunction "1_1") (pintype "passive"))
      (node (ref "R20") (pin "1") (pinfunction "1_1") (pintype "passive"))
      (node (ref "R30") (pin "1") (pinfunction "1_1") (pintype "passive"))
      (node (ref "U11") (pin "2") (pinfunction "VIN_2") (pintype "power_in"))
      (node (ref "U6") (pin "1") (pinfunction "EN_1") (pintype "input"))
      (node (ref "U6") (pin "2") (pinfunction "VIN_2") (pintype "power_in"))
      (node (ref "U7") (pin "2") (pinfunction "VIN_2") (pintype "power_in"))
      (node (ref "U8") (pin "2") (pinfunction "VIN_2") (pintype "power_in"))
      (node (ref "U9") (pin "2") (pinfunction "VIN_2") (pintype "power_in"))
      (node (ref "pwr+1") (pin "1") (pinfunction "Pin_1") (pintype "passive"))
    )
    (net (code "26") (name "VTTREF") (class "Default")
      (node (ref "C130") (pin "1") (pinfunction "1_1") (pintype "passive"))
      (node (ref "C131") (pin "1") (pinfunction "1_1") (pintype "passive"))
      (node (ref "C132") (pin "1") (pinfunction "1_1") (pintype "passive"))
      (node (ref "C133") (pin "1") (pinfunction "1_1") (pintype "passive"))
      (node (ref "C134") (pin "1") (pinfunction "1_1") (pintype "passive"))
      (node (ref "C135") (pin "1") (pinfunction "1_1") (pintype "passive"))
      (node (ref "C136") (pin "1") (pinfunction "1_1") (pintype "passive"))
      (node (ref "C137") (pin "1") (pinfunction "1_1") (pintype "passive"))
      (node (ref "C138") (pin "1") (pinfunction "1_1") (pintype "passive"))
      (node (ref "C151") (pin "1") (pinfunction "1_1") (pintype "passive"))
      (node (ref "C152") (pin "1") (pinfunction "1_1") (pintype "passive"))
    )
  )
)
